# RC__RX.net
KiCad netlist of a schematic drawn in EAGLE
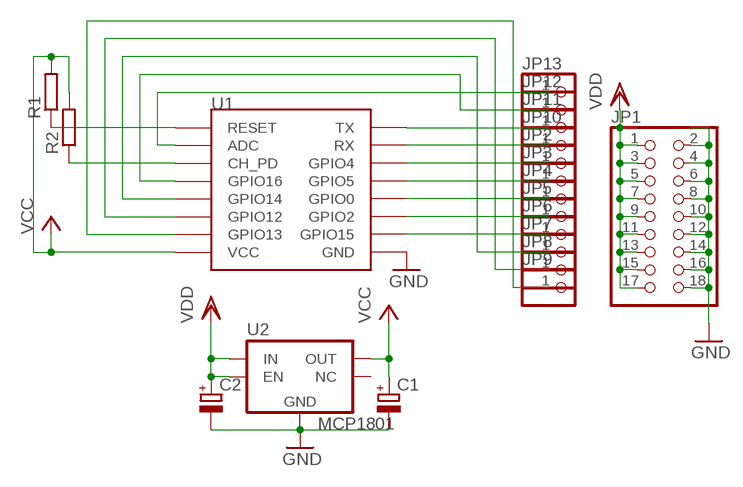
[diagram p0: schematic, sheet 1]

(export (version "E")
  (design (tool "Eeschema 10.0.6"))
  (components
    (comp (ref "C1")
      (value "CPOL-EUA/3216-18W")
      (footprint "eagle-import:A_3216-18W")
      (libsource (lib "eagle-import") (part "CPOL-EUA/3216-18W"))
    )
    (comp (ref "C2")
      (value "CPOL-EUA/3216-18W")
      (footprint "eagle-import:A_3216-18W")
      (libsource (lib "eagle-import") (part "CPOL-EUA/3216-18W"))
    )
    (comp (ref "JP1")
      (value "PINHD-2X9")
      (footprint "eagle-import:2X09")
      (libsource (lib "eagle-import") (part "PINHD-2X9"))
    )
    (comp (ref "JP2")
      (value "PINHD-1X1")
      (footprint "eagle-import:1X01")
      (libsource (lib "eagle-import") (part "PINHD-1X1"))
    )
    (comp (ref "JP3")
      (value "PINHD-1X1")
      (footprint "eagle-import:1X01")
      (libsource (lib "eagle-import") (part "PINHD-1X1"))
    )
    (comp (ref "JP4")
      (value "PINHD-1X1")
      (footprint "eagle-import:1X01")
      (libsource (lib "eagle-import") (part "PINHD-1X1"))
    )
    (comp (ref "JP5")
      (value "PINHD-1X1")
      (footprint "eagle-import:1X01")
      (libsource (lib "eagle-import") (part "PINHD-1X1"))
    )
    (comp (ref "JP6")
      (value "PINHD-1X1")
      (footprint "eagle-import:1X01")
      (libsource (lib "eagle-import") (part "PINHD-1X1"))
    )
    (comp (ref "JP7")
      (value "PINHD-1X1")
      (footprint "eagle-import:1X01")
      (libsource (lib "eagle-import") (part "PINHD-1X1"))
    )
    (comp (ref "JP8")
      (value "PINHD-1X1")
      (footprint "eagle-import:1X01")
      (libsource (lib "eagle-import") (part "PINHD-1X1"))
    )
    (comp (ref "JP9")
      (value "PINHD-1X1")
      (footprint "eagle-import:1X01")
      (libsource (lib "eagle-import") (part "PINHD-1X1"))
    )
    (comp (ref "JP10")
      (value "PINHD-1X1")
      (footprint "eagle-import:1X01")
      (libsource (lib "eagle-import") (part "PINHD-1X1"))
    )
    (comp (ref "JP11")
      (value "PINHD-1X1")
      (footprint "eagle-import:1X01")
      (libsource (lib "eagle-import") (part "PINHD-1X1"))
    )
    (comp (ref "JP12")
      (value "PINHD-1X1")
      (footprint "eagle-import:1X01")
      (libsource (lib "eagle-import") (part "PINHD-1X1"))
    )
    (comp (ref "JP13")
      (value "PINHD-1X1")
      (footprint "eagle-import:1X01")
      (libsource (lib "eagle-import") (part "PINHD-1X1"))
    )
    (comp (ref "R1")
      (value "R-EU_R0805")
      (footprint "eagle-import:R0805")
      (libsource (lib "eagle-import") (part "R-EU_R0805"))
    )
    (comp (ref "R2")
      (value "R-EU_R0805")
      (footprint "eagle-import:R0805")
      (libsource (lib "eagle-import") (part "R-EU_R0805"))
    )
    (comp (ref "U1")
      (value "ESP12")
      (footprint "eagle-import:ESP12")
      (libsource (lib "eagle-import") (part "ESP12"))
    )
    (comp (ref "U2")
      (value "MCP1801")
      (footprint "eagle-import:SOT23-5")
      (libsource (lib "eagle-import") (part "MCP1801"))
    )
  )
  (nets
    (net (code "1") (name "GND") (class "Default")
      (node (ref "C1") (pin "-") (pinfunction "-_-") (pintype "passive"))
      (node (ref "C2") (pin "-") (pinfunction "-_-") (pintype "passive"))
      (node (ref "JP1") (pin "10") (pinfunction "10_10") (pintype "passive"))
      (node (ref "JP1") (pin "12") (pinfunction "12_12") (pintype "passive"))
      (node (ref "JP1") (pin "14") (pinfunction "14_14") (pintype "passive"))
      (node (ref "JP1") (pin "16") (pinfunction "16_16") (pintype "passive"))
      (node (ref "JP1") (pin "18") (pinfunction "18_18") (pintype "passive"))
      (node (ref "JP1") (pin "2") (pinfunction "2_2") (pintype "passive"))
      (node (ref "JP1") (pin "4") (pinfunction "4_4") (pintype "passive"))
      (node (ref "JP1") (pin "6") (pinfunction "6_6") (pintype "passive"))
      (node (ref "JP1") (pin "8") (pinfunction "8_8") (pintype "passive"))
      (node (ref "U1") (pin "GND") (pinfunction "GND_GND") (pintype "bidirectional"))
      (node (ref "U2") (pin "2") (pinfunction "GND_2") (pintype "power_in"))
    )
    (net (code "2") (name "Net-(JP2-Pad1)") (class "Default")
      (node (ref "JP2") (pin "1") (pinfunction "1_1") (pintype "passive"))
      (node (ref "U1") (pin "GPIO4") (pinfunction "GPIO4_GPIO4") (pintype "bidirectional"))
    )
    (net (code "3") (name "Net-(JP3-Pad1)") (class "Default")
      (node (ref "JP3") (pin "1") (pinfunction "1_1") (pintype "passive"))
      (node (ref "U1") (pin "GPIO5") (pinfunction "GPIO5_GPIO5") (pintype "bidirectional"))
    )
    (net (code "4") (name "Net-(JP4-Pad1)") (class "Default")
      (node (ref "JP4") (pin "1") (pinfunction "1_1") (pintype "passive"))
      (node (ref "U1") (pin "GPIO0") (pinfunction "GPIO0_GPIO0") (pintype "bidirectional"))
    )
    (net (code "5") (name "Net-(JP5-Pad1)") (class "Default")
      (node (ref "JP5") (pin "1") (pinfunction "1_1") (pintype "passive"))
      (node (ref "U1") (pin "GPIO2") (pinfunction "GPIO2_GPIO2") (pintype "bidirectional"))
    )
    (net (code "6") (name "Net-(JP6-Pad1)") (class "Default")
      (node (ref "JP6") (pin "1") (pinfunction "1_1") (pintype "passive"))
      (node (ref "U1") (pin "GPIO15") (pinfunction "GPIO15_GPIO15") (pintype "bidirectional"))
    )
    (net (code "7") (name "Net-(JP7-Pad1)") (class "Default")
      (node (ref "JP7") (pin "1") (pinfunction "1_1") (pintype "passive"))
      (node (ref "U1") (pin "GPIO14") (pinfunction "GPIO14_GPIO14") (pintype "bidirectional"))
    )
    (net (code "8") (name "Net-(JP8-Pad1)") (class "Default")
      (node (ref "JP8") (pin "1") (pinfunction "1_1") (pintype "passive"))
      (node (ref "U1") (pin "GPIO12") (pinfunction "GPIO12_GPIO12") (pintype "bidirectional"))
    )
    (net (code "9") (name "Net-(JP9-Pad1)") (class "Default")
      (node (ref "JP9") (pin "1") (pinfunction "1_1") (pintype "passive"))
      (node (ref "U1") (pin "GPIO13") (pinfunction "GPIO13_GPIO13") (pintype "bidirectional"))
    )
    (net (code "10") (name "Net-(JP10-Pad1)") (class "Default")
      (node (ref "JP10") (pin "1") (pinfunction "1_1") (pintype "passive"))
      (node (ref "U1") (pin "RX") (pinfunction "RX_RX") (pintype "bidirectional"))
    )
    (net (code "11") (name "Net-(JP11-Pad1)") (class "Default")
      (node (ref "JP11") (pin "1") (pinfunction "1_1") (pintype "passive"))
      (node (ref "U1") (pin "TX") (pinfunction "TX_TX") (pintype "bidirectional"))
    )
    (net (code "12") (name "Net-(JP12-Pad1)") (class "Default")
      (node (ref "JP12") (pin "1") (pinfunction "1_1") (pintype "passive"))
      (node (ref "U1") (pin "GPIO16") (pinfunction "GPIO16_GPIO16") (pintype "bidirectional"))
    )
    (net (code "13") (name "Net-(JP13-Pad1)") (class "Default")
      (node (ref "JP13") (pin "1") (pinfunction "1_1") (pintype "passive"))
      (node (ref "U1") (pin "ADC") (pinfunction "ADC_ADC") (pintype "bidirectional"))
    )
    (net (code "14") (name "Net-(R1-Pad1)") (class "Default")
      (node (ref "R1") (pin "1") (pinfunction "1_1") (pintype "passive"))
      (node (ref "U1") (pin "RESET") (pinfunction "RESET_RESET") (pintype "bidirectional"))
    )
    (net (code "15") (name "Net-(R2-Pad1)") (class "Default")
      (node (ref "R2") (pin "1") (pinfunction "1_1") (pintype "passive"))
      (node (ref "U1") (pin "CH_PD") (pinfunction "CH_PD_CH_PD") (pintype "bidirectional"))
    )
    (net (code "16") (name "VCC") (class "Default")
      (node (ref "C1") (pin "+") (pinfunction "+_+") (pintype "passive"))
      (node (ref "R1") (pin "2") (pinfunction "2_2") (pintype "passive"))
      (node (ref "R2") (pin "2") (pinfunction "2_2") (pintype "passive"))
      (node (ref "U1") (pin "VCC") (pinfunction "VCC_VCC") (pintype "bidirectional"))
      (node (ref "U2") (pin "5") (pinfunction "OUT_5") (pintype "power_in"))
    )
    (net (code "17") (name "VDD") (class "Default")
      (node (ref "C2") (pin "+") (pinfunction "+_+") (pintype "passive"))
      (node (ref "JP1") (pin "1") (pinfunction "1_1") (pintype "passive"))
      (node (ref "JP1") (pin "11") (pinfunction "11_11") (pintype "passive"))
      (node (ref "JP1") (pin "13") (pinfunction "13_13") (pintype "passive"))
      (node (ref "JP1") (pin "15") (pinfunction "15_15") (pintype "passive"))
      (node (ref "JP1") (pin "17") (pinfunction "17_17") (pintype "passive"))
      (node (ref "JP1") (pin "3") (pinfunction "3_3") (pintype "passive"))
      (node (ref "JP1") (pin "5") (pinfunction "5_5") (pintype "passive"))
      (node (ref "JP1") (pin "7") (pinfunction "7_7") (pintype "passive"))
      (node (ref "JP1") (pin "9") (pinfunction "9_9") (pintype "passive"))
      (node (ref "U2") (pin "1") (pinfunction "IN_1") (pintype "power_in"))
      (node (ref "U2") (pin "3") (pinfunction "EN_3") (pintype "input"))
    )
    (net (code "18") (name "unconnected-(U2-NC-Pad4)") (class "Default")
      (node (ref "U2") (pin "4") (pinfunction "NC_4") (pintype "no_connect"))
    )
  )
)
